# buckler.net
KiCad netlist of a schematic drawn in EAGLE
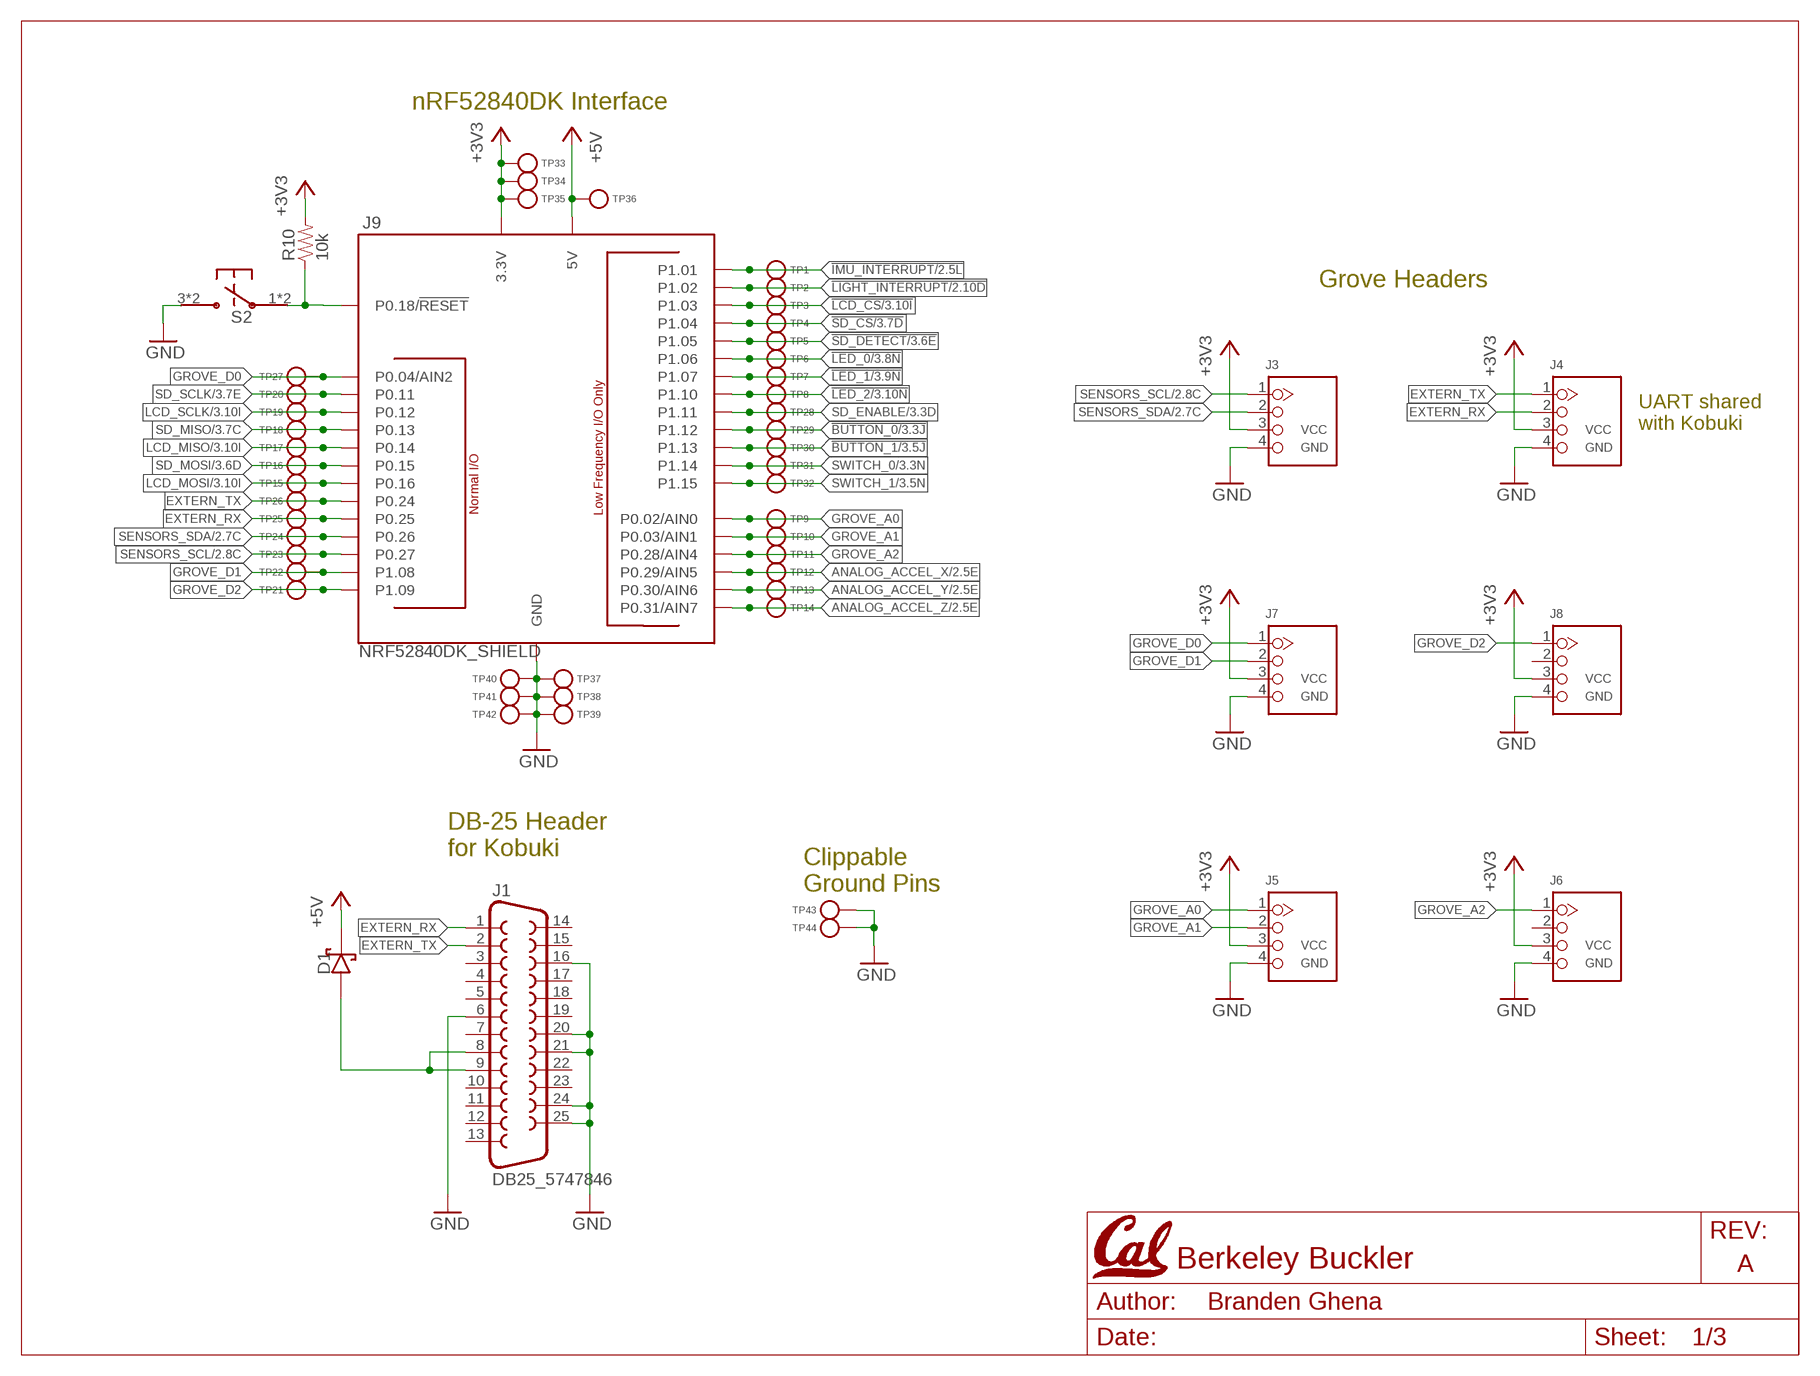
[diagram p0: schematic, sheet 1]
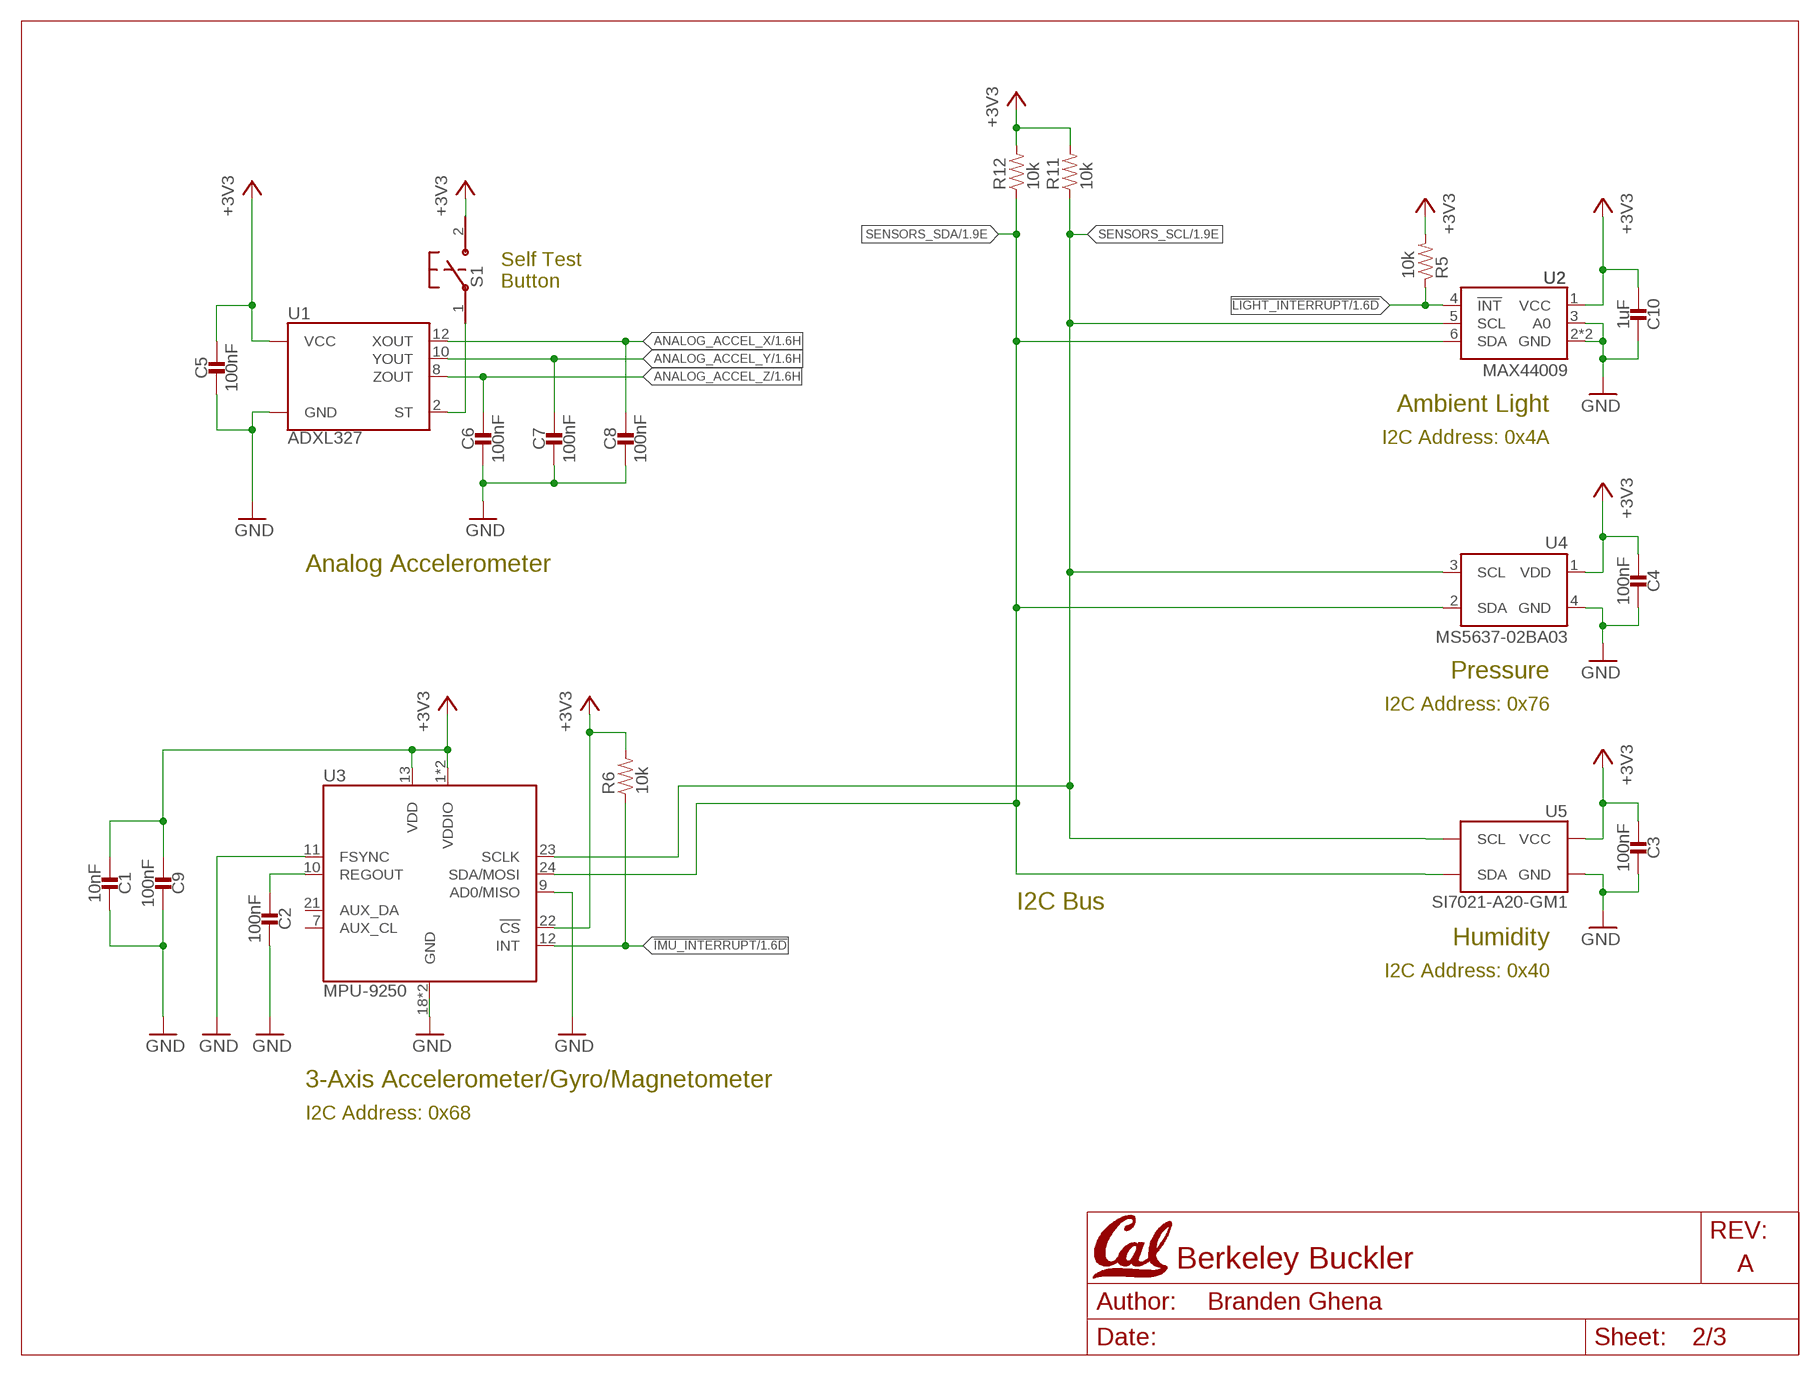
[diagram p1: schematic, sheet 2]
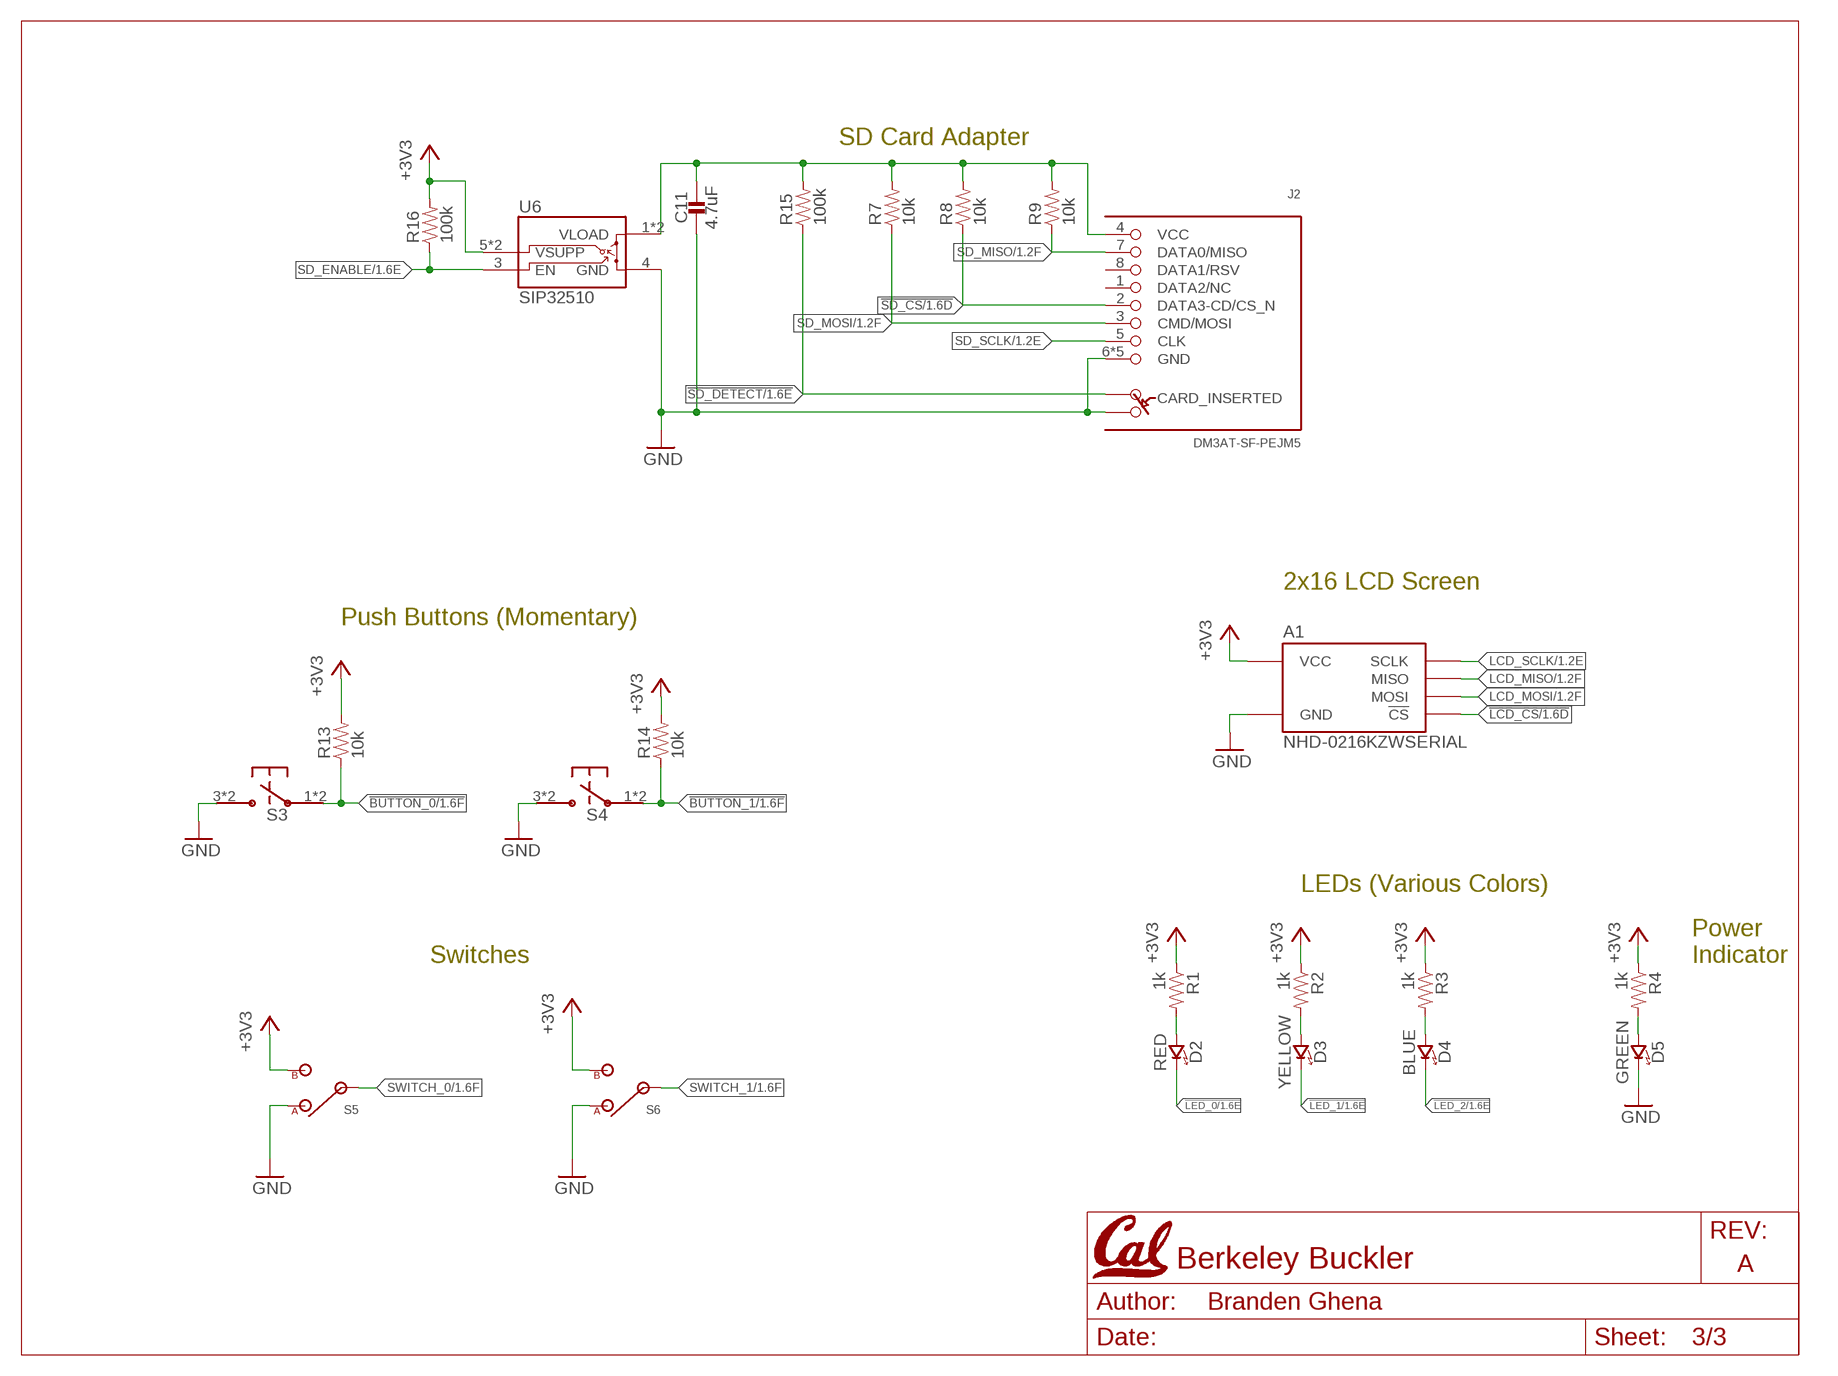
[diagram p2: schematic, sheet 3]

(export (version "E")
  (design (tool "Eeschema 10.0.6"))
  (components
    (comp (ref "D1")
      (value "DIODE_SCHOTTKYSOD323")
      (footprint "eagle-import:SOD323")
      (description "DIODE SCHOTTKY 30V 500MA SOD323")
      (fields (field (name "MANUFACTURER") "Diodes Incorporated") (field (name "MPN") "B0530WS-7-F"))
      (libsource (lib "eagle-import") (part "DIODE_SCHOTTKYSOD323"))
    )
    (comp (ref "J1")
      (value "DB25_5747846")
      (footprint "eagle-import:DB25_5747846")
      (description "CONN D-SUB RCPT 25POS R/A SOLDER")
      (fields (field (name "MANUFACTURER") "TE Connectivity AMP Connectors") (field (name "MPN") "5747846-4"))
      (libsource (lib "eagle-import") (part "DB25_5747846"))
    )
    (comp (ref "J3")
      (value "4P-2.0")
      (footprint "eagle-import:HW4-2.0")
      (description "Grove - Universal 4 pin connector")
      (fields (field (name "MANUFACTURER") "Seeed Studio") (field (name "MPN") "110990030"))
      (libsource (lib "eagle-import") (part "GROVE-CONNECTOR-DIP(4P-2.0)"))
    )
    (comp (ref "J4")
      (value "4P-2.0")
      (footprint "eagle-import:HW4-2.0")
      (description "Grove - Universal 4 pin connector")
      (fields (field (name "MANUFACTURER") "Seeed Studio") (field (name "MPN") "110990030"))
      (libsource (lib "eagle-import") (part "GROVE-CONNECTOR-DIP(4P-2.0)"))
    )
    (comp (ref "J5")
      (value "4P-2.0")
      (footprint "eagle-import:HW4-2.0")
      (description "Grove - Universal 4 pin connector")
      (fields (field (name "MANUFACTURER") "Seeed Studio") (field (name "MPN") "110990030"))
      (libsource (lib "eagle-import") (part "GROVE-CONNECTOR-DIP(4P-2.0)"))
    )
    (comp (ref "J6")
      (value "4P-2.0")
      (footprint "eagle-import:HW4-2.0")
      (description "Grove - Universal 4 pin connector")
      (fields (field (name "MANUFACTURER") "Seeed Studio") (field (name "MPN") "110990030"))
      (libsource (lib "eagle-import") (part "GROVE-CONNECTOR-DIP(4P-2.0)"))
    )
    (comp (ref "J7")
      (value "4P-2.0")
      (footprint "eagle-import:HW4-2.0")
      (description "Grove - Universal 4 pin connector")
      (fields (field (name "MANUFACTURER") "Seeed Studio") (field (name "MPN") "110990030"))
      (libsource (lib "eagle-import") (part "GROVE-CONNECTOR-DIP(4P-2.0)"))
    )
    (comp (ref "J8")
      (value "4P-2.0")
      (footprint "eagle-import:HW4-2.0")
      (description "Grove - Universal 4 pin connector")
      (fields (field (name "MANUFACTURER") "Seeed Studio") (field (name "MPN") "110990030"))
      (libsource (lib "eagle-import") (part "GROVE-CONNECTOR-DIP(4P-2.0)"))
    )
    (comp (ref "J9")
      (value "NRF52840DK_SHIELD")
      (footprint "eagle-import:NRF52840DK_SHIELD")
      (description "Headers for nRF52840DK. There are 6 separate headers to be installed through the board.")
      (libsource (lib "eagle-import") (part "NRF52840DK_SHIELD"))
    )
    (comp (ref "R10")
      (value "10k")
      (footprint "eagle-import:0402_RES")
      (description "RES SMD 10K OHM 1% 1/16W 0402")
      (fields (field (name "MANUFACTURER") "Samsung Electro-Mechanics") (field (name "MPN") "RC1005F103CS"))
      (libsource (lib "eagle-import") (part "RESISTOR0402_RES"))
    )
    (comp (ref "S2")
      (value "PTS645SM43SMTR92")
      (footprint "eagle-import:PTS645")
      (description "SWITCH TACTILE SPST-NO 0.05A 12V")
      (fields (field (name "MANUFACTURER") "C&K") (field (name "MPN") "PTS645SM43SMTR92 LFS"))
      (libsource (lib "eagle-import") (part "PTS645SM43SMTR92"))
    )
    (comp (ref "TP1")
      (value "TEST_POINT_0.040IN")
      (footprint "eagle-import:TESTPOINT_0.040IN")
      (libsource (lib "eagle-import") (part "TEST_POINT_0.040IN"))
    )
    (comp (ref "TP2")
      (value "TEST_POINT_0.040IN")
      (footprint "eagle-import:TESTPOINT_0.040IN")
      (libsource (lib "eagle-import") (part "TEST_POINT_0.040IN"))
    )
    (comp (ref "TP3")
      (value "TEST_POINT_0.040IN")
      (footprint "eagle-import:TESTPOINT_0.040IN")
      (libsource (lib "eagle-import") (part "TEST_POINT_0.040IN"))
    )
    (comp (ref "TP4")
      (value "TEST_POINT_0.040IN")
      (footprint "eagle-import:TESTPOINT_0.040IN")
      (libsource (lib "eagle-import") (part "TEST_POINT_0.040IN"))
    )
    (comp (ref "TP5")
      (value "TEST_POINT_0.040IN")
      (footprint "eagle-import:TESTPOINT_0.040IN")
      (libsource (lib "eagle-import") (part "TEST_POINT_0.040IN"))
    )
    (comp (ref "TP6")
      (value "TEST_POINT_0.040IN")
      (footprint "eagle-import:TESTPOINT_0.040IN")
      (libsource (lib "eagle-import") (part "TEST_POINT_0.040IN"))
    )
    (comp (ref "TP7")
      (value "TEST_POINT_0.040IN")
      (footprint "eagle-import:TESTPOINT_0.040IN")
      (libsource (lib "eagle-import") (part "TEST_POINT_0.040IN"))
    )
    (comp (ref "TP8")
      (value "TEST_POINT_0.040IN")
      (footprint "eagle-import:TESTPOINT_0.040IN")
      (libsource (lib "eagle-import") (part "TEST_POINT_0.040IN"))
    )
    (comp (ref "TP9")
      (value "TEST_POINT_0.040IN")
      (footprint "eagle-import:TESTPOINT_0.040IN")
      (libsource (lib "eagle-import") (part "TEST_POINT_0.040IN"))
    )
    (comp (ref "TP10")
      (value "TEST_POINT_0.040IN")
      (footprint "eagle-import:TESTPOINT_0.040IN")
      (libsource (lib "eagle-import") (part "TEST_POINT_0.040IN"))
    )
    (comp (ref "TP11")
      (value "TEST_POINT_0.040IN")
      (footprint "eagle-import:TESTPOINT_0.040IN")
      (libsource (lib "eagle-import") (part "TEST_POINT_0.040IN"))
    )
    (comp (ref "TP12")
      (value "TEST_POINT_0.040IN")
      (footprint "eagle-import:TESTPOINT_0.040IN")
      (libsource (lib "eagle-import") (part "TEST_POINT_0.040IN"))
    )
    (comp (ref "TP13")
      (value "TEST_POINT_0.040IN")
      (footprint "eagle-import:TESTPOINT_0.040IN")
      (libsource (lib "eagle-import") (part "TEST_POINT_0.040IN"))
    )
    (comp (ref "TP14")
      (value "TEST_POINT_0.040IN")
      (footprint "eagle-import:TESTPOINT_0.040IN")
      (libsource (lib "eagle-import") (part "TEST_POINT_0.040IN"))
    )
    (comp (ref "TP15")
      (value "TEST_POINT_0.040IN")
      (footprint "eagle-import:TESTPOINT_0.040IN")
      (libsource (lib "eagle-import") (part "TEST_POINT_0.040IN"))
    )
    (comp (ref "TP16")
      (value "TEST_POINT_0.040IN")
      (footprint "eagle-import:TESTPOINT_0.040IN")
      (libsource (lib "eagle-import") (part "TEST_POINT_0.040IN"))
    )
    (comp (ref "TP17")
      (value "TEST_POINT_0.040IN")
      (footprint "eagle-import:TESTPOINT_0.040IN")
      (libsource (lib "eagle-import") (part "TEST_POINT_0.040IN"))
    )
    (comp (ref "TP18")
      (value "TEST_POINT_0.040IN")
      (footprint "eagle-import:TESTPOINT_0.040IN")
      (libsource (lib "eagle-import") (part "TEST_POINT_0.040IN"))
    )
    (comp (ref "TP19")
      (value "TEST_POINT_0.040IN")
      (footprint "eagle-import:TESTPOINT_0.040IN")
      (libsource (lib "eagle-import") (part "TEST_POINT_0.040IN"))
    )
    (comp (ref "TP20")
      (value "TEST_POINT_0.040IN")
      (footprint "eagle-import:TESTPOINT_0.040IN")
      (libsource (lib "eagle-import") (part "TEST_POINT_0.040IN"))
    )
    (comp (ref "TP21")
      (value "TEST_POINT_0.040IN")
      (footprint "eagle-import:TESTPOINT_0.040IN")
      (libsource (lib "eagle-import") (part "TEST_POINT_0.040IN"))
    )
    (comp (ref "TP22")
      (value "TEST_POINT_0.040IN")
      (footprint "eagle-import:TESTPOINT_0.040IN")
      (libsource (lib "eagle-import") (part "TEST_POINT_0.040IN"))
    )
    (comp (ref "TP23")
      (value "TEST_POINT_0.040IN")
      (footprint "eagle-import:TESTPOINT_0.040IN")
      (libsource (lib "eagle-import") (part "TEST_POINT_0.040IN"))
    )
    (comp (ref "TP24")
      (value "TEST_POINT_0.040IN")
      (footprint "eagle-import:TESTPOINT_0.040IN")
      (libsource (lib "eagle-import") (part "TEST_POINT_0.040IN"))
    )
    (comp (ref "TP25")
      (value "TEST_POINT_0.040IN")
      (footprint "eagle-import:TESTPOINT_0.040IN")
      (libsource (lib "eagle-import") (part "TEST_POINT_0.040IN"))
    )
    (comp (ref "TP26")
      (value "TEST_POINT_0.040IN")
      (footprint "eagle-import:TESTPOINT_0.040IN")
      (libsource (lib "eagle-import") (part "TEST_POINT_0.040IN"))
    )
    (comp (ref "TP27")
      (value "TEST_POINT_0.040IN")
      (footprint "eagle-import:TESTPOINT_0.040IN")
      (libsource (lib "eagle-import") (part "TEST_POINT_0.040IN"))
    )
    (comp (ref "TP28")
      (value "TEST_POINT_0.040IN")
      (footprint "eagle-import:TESTPOINT_0.040IN")
      (libsource (lib "eagle-import") (part "TEST_POINT_0.040IN"))
    )
    (comp (ref "TP29")
      (value "TEST_POINT_0.040IN")
      (footprint "eagle-import:TESTPOINT_0.040IN")
      (libsource (lib "eagle-import") (part "TEST_POINT_0.040IN"))
    )
    (comp (ref "TP30")
      (value "TEST_POINT_0.040IN")
      (footprint "eagle-import:TESTPOINT_0.040IN")
      (libsource (lib "eagle-import") (part "TEST_POINT_0.040IN"))
    )
    (comp (ref "TP31")
      (value "TEST_POINT_0.040IN")
      (footprint "eagle-import:TESTPOINT_0.040IN")
      (libsource (lib "eagle-import") (part "TEST_POINT_0.040IN"))
    )
    (comp (ref "TP32")
      (value "TEST_POINT_0.040IN")
      (footprint "eagle-import:TESTPOINT_0.040IN")
      (libsource (lib "eagle-import") (part "TEST_POINT_0.040IN"))
    )
    (comp (ref "TP33")
      (value "TEST_POINT_0.040IN")
      (footprint "eagle-import:TESTPOINT_0.040IN")
      (libsource (lib "eagle-import") (part "TEST_POINT_0.040IN"))
    )
    (comp (ref "TP34")
      (value "TEST_POINT_0.040IN")
      (footprint "eagle-import:TESTPOINT_0.040IN")
      (libsource (lib "eagle-import") (part "TEST_POINT_0.040IN"))
    )
    (comp (ref "TP35")
      (value "TEST_POINT_0.040IN")
      (footprint "eagle-import:TESTPOINT_0.040IN")
      (libsource (lib "eagle-import") (part "TEST_POINT_0.040IN"))
    )
    (comp (ref "TP36")
      (value "TEST_POINT_0.040IN")
      (footprint "eagle-import:TESTPOINT_0.040IN")
      (libsource (lib "eagle-import") (part "TEST_POINT_0.040IN"))
    )
    (comp (ref "TP37")
      (value "TEST_POINT_0.040IN")
      (footprint "eagle-import:TESTPOINT_0.040IN")
      (libsource (lib "eagle-import") (part "TEST_POINT_0.040IN"))
    )
    (comp (ref "TP38")
      (value "TEST_POINT_0.040IN")
      (footprint "eagle-import:TESTPOINT_0.040IN")
      (libsource (lib "eagle-import") (part "TEST_POINT_0.040IN"))
    )
    (comp (ref "TP39")
      (value "TEST_POINT_0.040IN")
      (footprint "eagle-import:TESTPOINT_0.040IN")
      (libsource (lib "eagle-import") (part "TEST_POINT_0.040IN"))
    )
    (comp (ref "TP40")
      (value "TEST_POINT_0.040IN")
      (footprint "eagle-import:TESTPOINT_0.040IN")
      (libsource (lib "eagle-import") (part "TEST_POINT_0.040IN"))
    )
    (comp (ref "TP41")
      (value "TEST_POINT_0.040IN")
      (footprint "eagle-import:TESTPOINT_0.040IN")
      (libsource (lib "eagle-import") (part "TEST_POINT_0.040IN"))
    )
    (comp (ref "TP42")
      (value "TEST_POINT_0.040IN")
      (footprint "eagle-import:TESTPOINT_0.040IN")
      (libsource (lib "eagle-import") (part "TEST_POINT_0.040IN"))
    )
    (comp (ref "TP43")
      (value "TEST_POINT_0.078IN")
      (footprint "eagle-import:TESTPOINT_0.078IN")
      (description "TERM TURRET SINGLE L=4.75MM TIN")
      (fields (field (name "MANUFACTURER") "Keystone Electronics") (field (name "MPN") "1520-2"))
      (libsource (lib "eagle-import") (part "TEST_POINT_0.078IN"))
    )
    (comp (ref "TP44")
      (value "TEST_POINT_0.078IN")
      (footprint "eagle-import:TESTPOINT_0.078IN")
      (description "TERM TURRET SINGLE L=4.75MM TIN")
      (fields (field (name "MANUFACTURER") "Keystone Electronics") (field (name "MPN") "1520-2"))
      (libsource (lib "eagle-import") (part "TEST_POINT_0.078IN"))
    )
    (comp (ref "A1")
      (value "NHD-0216KZWSERIAL")
      (footprint "eagle-import:NHD-0216KZW")
      (libsource (lib "eagle-import") (part "NHD-0216KZWSERIAL"))
    )
    (comp (ref "C11")
      (value "4.7uF")
      (footprint "eagle-import:0402_CAP")
      (description "CAP CER 4.7UF 10V X5R 0402")
      (fields
        (field (name "MANUFACTURER") "Samsung Electro-Mechanics")
        (field (name "MPN") "CL05A475KP5NRNC")
      )
      (libsource (lib "eagle-import") (part "CAPACITOR0402_CAP"))
    )
    (comp (ref "D2")
      (value "RED")
      (footprint "eagle-import:LED-0603")
      (description "LED RED CLEAR CHIP SMD")
      (fields (field (name "MANUFACTURER") "Lite-On Inc.") (field (name "MPN") "LTST-C190KRKT"))
      (libsource (lib "eagle-import") (part "LED0603"))
    )
    (comp (ref "D3")
      (value "YELLOW")
      (footprint "eagle-import:LED-0603")
      (description "LED YELLOW CLEAR CHIP SMD")
      (fields (field (name "MANUFACTURER") "Lite-On Inc.") (field (name "MPN") "LTST-C190KSKT"))
      (libsource (lib "eagle-import") (part "LED0603"))
    )
    (comp (ref "D4")
      (value "BLUE")
      (footprint "eagle-import:LED-0603")
      (description "LED BLUE CLEAR SMD")
      (fields (field (name "MANUFACTURER") "Lite-On Inc.") (field (name "MPN") "LTST-C194TBKT"))
      (libsource (lib "eagle-import") (part "LED0603"))
    )
    (comp (ref "D5")
      (value "GREEN")
      (footprint "eagle-import:LED-0603")
      (description "LED GREEN CLEAR CHIP SMD")
      (fields (field (name "MANUFACTURER") "Lite-On Inc.") (field (name "MPN") "LTST-C190KGKT"))
      (libsource (lib "eagle-import") (part "LED0603"))
    )
    (comp (ref "J2")
      (value "DM3AT-SF-PEJM5")
      (footprint "eagle-import:DM3AT-SF-PEJM5")
      (fields (field (name "MANUFACTURER") "Hirose Electric Co Ltd"))
      (libsource (lib "eagle-import") (part "DM3AT-SF-PEJM5"))
    )
    (comp (ref "R1")
      (value "1k")
      (footprint "eagle-import:0402_RES")
      (description "RES SMD 1K OHM 1% 1/16W 0402")
      (fields (field (name "MANUFACTURER") "Stackpole Electronics") (field (name "MPN") "RMCF0402FT1K00"))
      (libsource (lib "eagle-import") (part "RESISTOR0402_RES"))
    )
    (comp (ref "R2")
      (value "1k")
      (footprint "eagle-import:0402_RES")
      (description "RES SMD 1K OHM 1% 1/16W 0402")
      (fields (field (name "MANUFACTURER") "Stackpole Electronics") (field (name "MPN") "RMCF0402FT1K00"))
      (libsource (lib "eagle-import") (part "RESISTOR0402_RES"))
    )
    (comp (ref "R3")
      (value "1k")
      (footprint "eagle-import:0402_RES")
      (description "RES SMD 1K OHM 1% 1/16W 0402")
      (fields (field (name "MANUFACTURER") "Stackpole Electronics") (field (name "MPN") "RMCF0402FT1K00"))
      (libsource (lib "eagle-import") (part "RESISTOR0402_RES"))
    )
    (comp (ref "R4")
      (value "1k")
      (footprint "eagle-import:0402_RES")
      (description "RES SMD 1K OHM 1% 1/16W 0402")
      (fields (field (name "MANUFACTURER") "Stackpole Electronics") (field (name "MPN") "RMCF0402FT1K00"))
      (libsource (lib "eagle-import") (part "RESISTOR0402_RES"))
    )
    (comp (ref "R7")
      (value "10k")
      (footprint "eagle-import:0402_RES")
      (description "RES SMD 10K OHM 1% 1/16W 0402")
      (fields (field (name "MANUFACTURER") "Samsung Electro-Mechanics") (field (name "MPN") "RC1005F103CS"))
      (libsource (lib "eagle-import") (part "RESISTOR0402_RES"))
    )
    (comp (ref "R8")
      (value "10k")
      (footprint "eagle-import:0402_RES")
      (description "RES SMD 10K OHM 1% 1/16W 0402")
      (fields (field (name "MANUFACTURER") "Samsung Electro-Mechanics") (field (name "MPN") "RC1005F103CS"))
      (libsource (lib "eagle-import") (part "RESISTOR0402_RES"))
    )
    (comp (ref "R9")
      (value "10k")
      (footprint "eagle-import:0402_RES")
      (description "RES SMD 10K OHM 1% 1/16W 0402")
      (fields (field (name "MANUFACTURER") "Samsung Electro-Mechanics") (field (name "MPN") "RC1005F103CS"))
      (libsource (lib "eagle-import") (part "RESISTOR0402_RES"))
    )
    (comp (ref "R13")
      (value "10k")
      (footprint "eagle-import:0402_RES")
      (description "RES SMD 10K OHM 1% 1/16W 0402")
      (fields (field (name "MANUFACTURER") "Samsung Electro-Mechanics") (field (name "MPN") "RC1005F103CS"))
      (libsource (lib "eagle-import") (part "RESISTOR0402_RES"))
    )
    (comp (ref "R14")
      (value "10k")
      (footprint "eagle-import:0402_RES")
      (description "RES SMD 10K OHM 1% 1/16W 0402")
      (fields (field (name "MANUFACTURER") "Samsung Electro-Mechanics") (field (name "MPN") "RC1005F103CS"))
      (libsource (lib "eagle-import") (part "RESISTOR0402_RES"))
    )
    (comp (ref "R15")
      (value "100k")
      (footprint "eagle-import:0402_RES")
      (description "RES SMD 100K OHM 1% 1/5W 0402")
      (fields (field (name "MANUFACTURER") "Vishay Dale") (field (name "MPN") "CRCW0402100KFKEDHP"))
      (libsource (lib "eagle-import") (part "RESISTOR0402_RES"))
    )
    (comp (ref "R16")
      (value "100k")
      (footprint "eagle-import:0402_RES")
      (description "RES SMD 100K OHM 1% 1/5W 0402")
      (fields (field (name "MANUFACTURER") "Vishay Dale") (field (name "MPN") "CRCW0402100KFKEDHP"))
      (libsource (lib "eagle-import") (part "RESISTOR0402_RES"))
    )
    (comp (ref "S3")
      (value "PTS645SM43SMTR92")
      (footprint "eagle-import:PTS645")
      (description "SWITCH TACTILE SPST-NO 0.05A 12V")
      (fields (field (name "MANUFACTURER") "C&K") (field (name "MPN") "PTS645SM43SMTR92 LFS"))
      (libsource (lib "eagle-import") (part "PTS645SM43SMTR92"))
    )
    (comp (ref "S4")
      (value "PTS645SM43SMTR92")
      (footprint "eagle-import:PTS645")
      (description "SWITCH TACTILE SPST-NO 0.05A 12V")
      (fields (field (name "MANUFACTURER") "C&K") (field (name "MPN") "PTS645SM43SMTR92 LFS"))
      (libsource (lib "eagle-import") (part "PTS645SM43SMTR92"))
    )
    (comp (ref "S5")
      (value "TE_SSA12/SPDT")
      (footprint "eagle-import:TE_SSA12_SPDT")
      (description "SWITCH SLIDE SPDT 100MA 30V")
      (fields
        (field (name "MANUFACTURER") "TE Connectivity ALCOSWITCH Switches")
        (field (name "MPN") "SSA12")
      )
      (libsource (lib "eagle-import") (part "TE_SSA12/SPDT"))
    )
    (comp (ref "S6")
      (value "TE_SSA12/SPDT")
      (footprint "eagle-import:TE_SSA12_SPDT")
      (description "SWITCH SLIDE SPDT 100MA 30V")
      (fields
        (field (name "MANUFACTURER") "TE Connectivity ALCOSWITCH Switches")
        (field (name "MPN") "SSA12")
      )
      (libsource (lib "eagle-import") (part "TE_SSA12/SPDT"))
    )
    (comp (ref "U6")
      (value "SIP32510")
      (footprint "eagle-import:TSOT23-6")
      (description "IC LOAD SWITCH SOT23-6")
      (fields (field (name "MANUFACTURER") "Vishay") (field (name "MPN") "SIP32510DT-T1-GE3"))
      (libsource (lib "eagle-import") (part "SIP32510"))
    )
    (comp (ref "C1")
      (value "10nF")
      (footprint "eagle-import:0402_CAP")
      (description "CAP CER 10000PF 25V X7R 0402")
      (fields (field (name "MANUFACTURER") "KEMET") (field (name "MPN") "C0402C103J3RACTU"))
      (libsource (lib "eagle-import") (part "CAPACITOR0402_CAP"))
    )
    (comp (ref "C2")
      (value "100nF")
      (footprint "eagle-import:0402_CAP")
      (description "CAP CER 0.1UF 16V X7R 0402")
      (fields (field (name "MANUFACTURER") "Murata") (field (name "MPN") "GCM155R71C104KA55D"))
      (libsource (lib "eagle-import") (part "CAPACITOR0402_CAP"))
    )
    (comp (ref "C3")
      (value "100nF")
      (footprint "eagle-import:0402_CAP")
      (description "CAP CER 0.1UF 16V X7R 0402")
      (fields (field (name "MANUFACTURER") "Murata") (field (name "MPN") "GCM155R71C104KA55D"))
      (libsource (lib "eagle-import") (part "CAPACITOR0402_CAP"))
    )
    (comp (ref "C4")
      (value "100nF")
      (footprint "eagle-import:0402_CAP")
      (description "CAP CER 0.1UF 16V X7R 0402")
      (fields (field (name "MANUFACTURER") "Murata") (field (name "MPN") "GCM155R71C104KA55D"))
      (libsource (lib "eagle-import") (part "CAPACITOR0402_CAP"))
    )
    (comp (ref "C5")
      (value "100nF")
      (footprint "eagle-import:0402_CAP")
      (description "CAP CER 0.1UF 16V X7R 0402")
      (fields (field (name "MANUFACTURER") "Murata") (field (name "MPN") "GCM155R71C104KA55D"))
      (libsource (lib "eagle-import") (part "CAPACITOR0402_CAP"))
    )
    (comp (ref "C6")
      (value "100nF")
      (footprint "eagle-import:0402_CAP")
      (description "CAP CER 0.1UF 16V X7R 0402")
      (fields (field (name "MANUFACTURER") "Murata") (field (name "MPN") "GCM155R71C104KA55D"))
      (libsource (lib "eagle-import") (part "CAPACITOR0402_CAP"))
    )
    (comp (ref "C7")
      (value "100nF")
      (footprint "eagle-import:0402_CAP")
      (description "CAP CER 0.1UF 16V X7R 0402")
      (fields (field (name "MANUFACTURER") "Murata") (field (name "MPN") "GCM155R71C104KA55D"))
      (libsource (lib "eagle-import") (part "CAPACITOR0402_CAP"))
    )
    (comp (ref "C8")
      (value "100nF")
      (footprint "eagle-import:0402_CAP")
      (description "CAP CER 0.1UF 16V X7R 0402")
      (fields (field (name "MANUFACTURER") "Murata") (field (name "MPN") "GCM155R71C104KA55D"))
      (libsource (lib "eagle-import") (part "CAPACITOR0402_CAP"))
    )
    (comp (ref "C9")
      (value "100nF")
      (footprint "eagle-import:0402_CAP")
      (description "CAP CER 0.1UF 16V X7R 0402")
      (fields (field (name "MANUFACTURER") "Murata") (field (name "MPN") "GCM155R71C104KA55D"))
      (libsource (lib "eagle-import") (part "CAPACITOR0402_CAP"))
    )
    (comp (ref "C10")
      (value "1uF")
      (footprint "eagle-import:0402_CAP")
      (description "CAP CER 1UF 10V X6S 0402")
      (fields
        (field (name "MANUFACTURER") "Samsung Electro-Mechanics")
        (field (name "MPN") "CL05X105KP5NNNC")
      )
      (libsource (lib "eagle-import") (part "CAPACITOR0402_CAP"))
    )
    (comp (ref "R5")
      (value "10k")
      (footprint "eagle-import:0402_RES")
      (description "RES SMD 10K OHM 1% 1/16W 0402")
      (fields (field (name "MANUFACTURER") "Samsung Electro-Mechanics") (field (name "MPN") "RC1005F103CS"))
      (libsource (lib "eagle-import") (part "RESISTOR0402_RES"))
    )
    (comp (ref "R6")
      (value "10k")
      (footprint "eagle-import:0402_RES")
      (description "RES SMD 10K OHM 1% 1/16W 0402")
      (fields (field (name "MANUFACTURER") "Samsung Electro-Mechanics") (field (name "MPN") "RC1005F103CS"))
      (libsource (lib "eagle-import") (part "RESISTOR0402_RES"))
    )
    (comp (ref "R11")
      (value "10k")
      (footprint "eagle-import:0402_RES")
      (description "RES SMD 10K OHM 1% 1/16W 0402")
      (fields (field (name "MANUFACTURER") "Samsung Electro-Mechanics") (field (name "MPN") "RC1005F103CS"))
      (libsource (lib "eagle-import") (part "RESISTOR0402_RES"))
    )
    (comp (ref "R12")
      (value "10k")
      (footprint "eagle-import:0402_RES")
      (description "RES SMD 10K OHM 1% 1/16W 0402")
      (fields (field (name "MANUFACTURER") "Samsung Electro-Mechanics") (field (name "MPN") "RC1005F103CS"))
      (libsource (lib "eagle-import") (part "RESISTOR0402_RES"))
    )
    (comp (ref "S1")
      (value "B3U-1000P")
      (footprint "eagle-import:B3U-1000P")
      (description "SWITCH TACTILE SPST-NO 0.05A 12V")
      (fields (field (name "MANUFACTURER") "Omron") (field (name "MPN") "B3U-1000P"))
      (libsource (lib "eagle-import") (part "B3U-1000P"))
    )
    (comp (ref "U1")
      (value "ADXL327")
      (footprint "eagle-import:LFCSP-16")
      (description "ACCELEROMETER 2G ANALOG 16LFCSP")
      (fields (field (name "MANUFACTURER") "Analog Devices Inc.") (field (name "MPN") "ADXL327BCPZ"))
      (libsource (lib "eagle-import") (part "ADXL327"))
    )
    (comp (ref "U2")
      (value "MAX44009")
      (footprint "eagle-import:UDFN-6-EXPOSED")
      (description "SENSOR AMBIENT LIGHT 6UTDFN")
      (fields
        (field (name "MANUFACTURER") "MAXIM")
        (field (name "MPN") "MAX44009EDT+T")
        (field (name "MANUFACTURER_1") "Maxim Integrated")
      )
      (libsource (lib "eagle-import") (part "MAX44009"))
    )
    (comp (ref "U3")
      (value "MPU-9250")
      (footprint "eagle-import:QFN-24_3MM")
      (description "IMU ACCEL/GYRO/MAG I2C/SPI 24QFN")
      (fields (field (name "MANUFACTURER") "TDK InvenSense"))
      (libsource (lib "eagle-import") (part "MPU-9250"))
    )
    (comp (ref "U4")
      (value "MS5637-02BA03")
      (footprint "eagle-import:4-SMD")
      (description "SENSOR 17.4PSIA I2C 24B 4-QFN")
      (fields (field (name "MANUFACTURER") "TE CONNECTIVITY") (field (name "MPN") "MS563702BA03-50"))
      (libsource (lib "eagle-import") (part "MS5637-02BA03"))
    )
    (comp (ref "U5")
      (value "SI7021-A20-GM1")
      (footprint "eagle-import:DFN-6_3MM")
      (description "SENS HUMI/TEMP 3.6V I2C 3% 6DFN")
      (fields (field (name "MANUFACTURER") "Silicon Labs") (field (name "MPN") "SI7021-A20-GM1 "))
      (libsource (lib "eagle-import") (part "SI7021-A20-GM1"))
    )
  )
  (nets
    (net (code "1") (name "+3V3") (class "Default")
      (node (ref "A1") (pin "2") (pinfunction "VCC_2") (pintype "bidirectional"))
      (node (ref "C1") (pin "1") (pinfunction "1_1") (pintype "bidirectional"))
      (node (ref "C10") (pin "1") (pinfunction "1_1") (pintype "bidirectional"))
      (node (ref "C3") (pin "1") (pinfunction "1_1") (pintype "bidirectional"))
      (node (ref "C4") (pin "1") (pinfunction "1_1") (pintype "bidirectional"))
      (node (ref "C5") (pin "1") (pinfunction "1_1") (pintype "bidirectional"))
      (node (ref "C9") (pin "1") (pinfunction "1_1") (pintype "bidirectional"))
      (node (ref "J3") (pin "3") (pinfunction "3_3") (pintype "bidirectional"))
      (node (ref "J4") (pin "3") (pinfunction "3_3") (pintype "bidirectional"))
      (node (ref "J5") (pin "3") (pinfunction "3_3") (pintype "bidirectional"))
      (node (ref "J6") (pin "3") (pinfunction "3_3") (pintype "bidirectional"))
      (node (ref "J7") (pin "3") (pinfunction "3_3") (pintype "bidirectional"))
      (node (ref "J8") (pin "3") (pinfunction "3_3") (pintype "bidirectional"))
      (node (ref "J9") (pin "3.3V@0") (pinfunction "3.3V_3.3V@0") (pintype "bidirectional"))
      (node (ref "J9") (pin "3.3V@1") (pinfunction "3.3V_3.3V@1") (pintype "bidirectional"))
      (node (ref "J9") (pin "3.3V@2") (pinfunction "3.3V_3.3V@2") (pintype "bidirectional"))
      (node (ref "R1") (pin "1") (pinfunction "1_1") (pintype "passive"))
      (node (ref "R10") (pin "2") (pinfunction "2_2") (pintype "passive"))
      (node (ref "R11") (pin "2") (pinfunction "2_2") (pintype "passive"))
      (node (ref "R12") (pin "2") (pinfunction "2_2") (pintype "passive"))
      (node (ref "R13") (pin "2") (pinfunction "2_2") (pintype "passive"))
      (node (ref "R14") (pin "2") (pinfunction "2_2") (pintype "passive"))
      (node (ref "R16") (pin "2") (pinfunction "2_2") (pintype "passive"))
      (node (ref "R2") (pin "1") (pinfunction "1_1") (pintype "passive"))
      (node (ref "R3") (pin "1") (pinfunction "1_1") (pintype "passive"))
      (node (ref "R4") (pin "1") (pinfunction "1_1") (pintype "passive"))
      (node (ref "R5") (pin "2") (pinfunction "2_2") (pintype "passive"))
      (node (ref "R6") (pin "2") (pinfunction "2_2") (pintype "passive"))
      (node (ref "S1") (pin "2") (pinfunction "P$2_2") (pintype "passive"))
      (node (ref "S5") (pin "2") (pinfunction "B_2") (pintype "bidirectional"))
      (node (ref "S6") (pin "2") (pinfunction "B_2") (pintype "bidirectional"))
      (node (ref "TP33") (pin "TESTPOINT") (pinfunction "TESTPOINT_TESTPOINT") (pintype "bidirectional"))
      (node (ref "TP34") (pin "TESTPOINT") (pinfunction "TESTPOINT_TESTPOINT") (pintype "bidirectional"))
      (node (ref "TP35") (pin "TESTPOINT") (pinfunction "TESTPOINT_TESTPOINT") (pintype "bidirectional"))
      (node (ref "U1") (pin "14") (pinfunction "VCC_14") (pintype "bidirectional"))
      (node (ref "U1") (pin "15") (pinfunction "VCC_15") (pintype "bidirectional"))
      (node (ref "U2") (pin "1") (pinfunction "VCC_1") (pintype "bidirectional"))
      (node (ref "U3") (pin "1") (pinfunction "VDDIO_1") (pintype "bidirectional"))
      (node (ref "U3") (pin "13") (pinfunction "VDD_13") (pintype "bidirectional"))
      (node (ref "U3") (pin "22") (pinfunction "~{CS}_22") (pintype "bidirectional"))
      (node (ref "U3") (pin "8") (pinfunction "VDDIO_8") (pintype "bidirectional"))
      (node (ref "U4") (pin "1") (pinfunction "VDD_1") (pintype "bidirectional"))
      (node (ref "U5") (pin "5") (pinfunction "VCC_5") (pintype "bidirectional"))
      (node (ref "U6") (pin "5") (pinfunction "VSUPP_5") (pintype "bidirectional"))
      (node (ref "U6") (pin "6") (pinfunction "VSUPP_6") (pintype "bidirectional"))
    )
    (net (code "2") (name "+5V") (class "Default")
      (node (ref "D1") (pin "P$1") (pinfunction "CATHODE_P$1") (pintype "bidirectional"))
      (node (ref "J9") (pin "5V") (pinfunction "5V_5V") (pintype "bidirectional"))
      (node (ref "TP36") (pin "TESTPOINT") (pinfunction "TESTPOINT_TESTPOINT") (pintype "bidirectional"))
    )
    (net (code "3") (name "ANALOG_ACCEL_X") (class "Default")
      (node (ref "C8") (pin "1") (pinfunction "1_1") (pintype "bidirectional"))
      (node (ref "J9") (pin "P0.29") (pinfunction "P0.29/AIN5_P0.29") (pintype "bidirectional"))
      (node (ref "TP12") (pin "TESTPOINT") (pinfunction "TESTPOINT_TESTPOINT") (pintype "bidirectional"))
      (node (ref "U1") (pin "12") (pinfunction "XOUT_12") (pintype "bidirectional"))
    )
    (net (code "4") (name "ANALOG_ACCEL_Y") (class "Default")
      (node (ref "C7") (pin "1") (pinfunction "1_1") (pintype "bidirectional"))
      (node (ref "J9") (pin "P0.30") (pinfunction "P0.30/AIN6_P0.30") (pintype "bidirectional"))
      (node (ref "TP13") (pin "TESTPOINT") (pinfunction "TESTPOINT_TESTPOINT") (pintype "bidirectional"))
      (node (ref "U1") (pin "10") (pinfunction "YOUT_10") (pintype "bidirectional"))
    )
    (net (code "5") (name "ANALOG_ACCEL_Z") (class "Default")
      (node (ref "C6") (pin "1") (pinfunction "1_1") (pintype "bidirectional"))
      (node (ref "J9") (pin "P0.31") (pinfunction "P0.31/AIN7_P0.31") (pintype "bidirectional"))
      (node (ref "TP14") (pin "TESTPOINT") (pinfunction "TESTPOINT_TESTPOINT") (pintype "bidirectional"))
      (node (ref "U1") (pin "8") (pinfunction "ZOUT_8") (pintype "bidirectional"))
    )
    (net (code "6") (name "EXTERN_RX") (class "Default")
      (node (ref "J1") (pin "1") (pinfunction "1_1") (pintype "passive"))
      (node (ref "J4") (pin "2") (pinfunction "2_2") (pintype "bidirectional"))
      (node (ref "J9") (pin "P0.25") (pinfunction "P0.25_P0.25") (pintype "bidirectional"))
      (node (ref "TP25") (pin "TESTPOINT") (pinfunction "TESTPOINT_TESTPOINT") (pintype "bidirectional"))
    )
    (net (code "7") (name "EXTERN_TX") (class "Default")
      (node (ref "J1") (pin "2") (pinfunction "2_2") (pintype "passive"))
      (node (ref "J4") (pin "1") (pinfunction "1_1") (pintype "bidirectional"))
      (node (ref "J9") (pin "P0.24") (pinfunction "P0.24_P0.24") (pintype "bidirectional"))
      (node (ref "TP26") (pin "TESTPOINT") (pinfunction "TESTPOINT_TESTPOINT") (pintype "bidirectional"))
    )
    (net (code "8") (name "GND") (class "Default")
      (node (ref "A1") (pin "1") (pinfunction "GND_1") (pintype "bidirectional"))
      (node (ref "C1") (pin "2") (pinfunction "2_2") (pintype "bidirectional"))
      (node (ref "C10") (pin "2") (pinfunction "2_2") (pintype "bidirectional"))
      (node (ref "C11") (pin "2") (pinfunction "2_2") (pintype "bidirectional"))
      (node (ref "C2") (pin "2") (pinfunction "2_2") (pintype "bidirectional"))
      (node (ref "C3") (pin "2") (pinfunction "2_2") (pintype "bidirectional"))
      (node (ref "C4") (pin "2") (pinfunction "2_2") (pintype "bidirectional"))
      (node (ref "C5") (pin "2") (pinfunction "2_2") (pintype "bidirectional"))
      (node (ref "C6") (pin "2") (pinfunction "2_2") (pintype "bidirectional"))
      (node (ref "C7") (pin "2") (pinfunction "2_2") (pintype "bidirectional"))
      (node (ref "C8") (pin "2") (pinfunction "2_2") (pintype "bidirectional"))
      (node (ref "C9") (pin "2") (pinfunction "2_2") (pintype "bidirectional"))
      (node (ref "D5") (pin "C") (pinfunction "CATHODE_C") (pintype "bidirectional"))
      (node (ref "J1") (pin "16") (pinfunction "16_16") (pintype "passive"))
      (node (ref "J1") (pin "20") (pinfunction "20_20") (pintype "passive"))
      (node (ref "J1") (pin "21") (pinfunction "21_21") (pintype "passive"))
      (node (ref "J1") (pin "24") (pinfunction "24_24") (pintype "passive"))
      (node (ref "J1") (pin "25") (pinfunction "25_25") (pintype "passive"))
      (node (ref "J1") (pin "6") (pinfunction "6_6") (pintype "passive"))
      (node (ref "J2") (pin "6") (pinfunction "GND_6") (pintype "bidirectional"))
      (node (ref "J2") (pin "B") (pinfunction "B_B") (pintype "bidirectional"))
      (node (ref "J2") (pin "MOUNT0") (pinfunction "GND_MOUNT0") (pintype "bidirectional"))
      (node (ref "J2") (pin "MOUNT1") (pinfunction "GND_MOUNT1") (pintype "bidirectional"))
      (node (ref "J2") (pin "MOUNT2") (pinfunction "GND_MOUNT2") (pintype "bidirectional"))
      (node (ref "J2") (pin "MOUNT3") (pinfunction "GND_MOUNT3") (pintype "bidirectional"))
      (node (ref "J3") (pin "4") (pinfunction "4_4") (pintype "bidirectional"))
      (node (ref "J4") (pin "4") (pinfunction "4_4") (pintype "bidirectional"))
      (node (ref "J5") (pin "4") (pinfunction "4_4") (pintype "bidirectional"))
      (node (ref "J6") (pin "4") (pinfunction "4_4") (pintype "bidirectional"))
      (node (ref "J7") (pin "4") (pinfunction "4_4") (pintype "bidirectional"))
      (node (ref "J8") (pin "4") (pinfunction "4_4") (pintype "bidirectional"))
      (node (ref "J9") (pin "GND@0") (pinfunction "GND_GND@0") (pintype "bidirectional"))
      (node (ref "J9") (pin "GND@1") (pinfunction "GND_GND@1") (pintype "bidirectional"))
      (node (ref "J9") (pin "GND@2") (pinfunction "GND_GND@2") (pintype "bidirectional"))
      (node (ref "J9") (pin "GND@3") (pinfunction "GND_GND@3") (pintype "bidirectional"))
      (node (ref "S2") (pin "3") (pinfunction "P$2_3") (pintype "passive"))
      (node (ref "S2") (pin "4") (pinfunction "P$2_4") (pintype "passive"))
      (node (ref "S3") (pin "3") (pinfunction "P$2_3") (pintype "passive"))
      (node (ref "S3") (pin "4") (pinfunction "P$2_4") (pintype "passive"))
      (node (ref "S4") (pin "3") (pinfunction "P$2_3") (pintype "passive"))
      (node (ref "S4") (pin "4") (pinfunction "P$2_4") (pintype "passive"))
      (node (ref "S5") (pin "1") (pinfunction "A_1") (pintype "bidirectional"))
      (node (ref "S6") (pin "1") (pinfunction "A_1") (pintype "bidirectional"))
      (node (ref "TP37") (pin "TESTPOINT") (pinfunction "TESTPOINT_TESTPOINT") (pintype "bidirectional"))
      (node (ref "TP38") (pin "TESTPOINT") (pinfunction "TESTPOINT_TESTPOINT") (pintype "bidirectional"))
      (node (ref "TP39") (pin "TESTPOINT") (pinfunction "TESTPOINT_TESTPOINT") (pintype "bidirectional"))
      (node (ref "TP40") (pin "TESTPOINT") (pinfunction "TESTPOINT_TESTPOINT") (pintype "bidirectional"))
      (node (ref "TP41") (pin "TESTPOINT") (pinfunction "TESTPOINT_TESTPOINT") (pintype "bidirectional"))
      (node (ref "TP42") (pin "TESTPOINT") (pinfunction "TESTPOINT_TESTPOINT") (pintype "bidirectional"))
      (node (ref "TP43") (pin "1") (pinfunction "TESTPOINT_1") (pintype "bidirectional"))
      (node (ref "TP44") (pin "1") (pinfunction "TESTPOINT_1") (pintype "bidirectional"))
      (node (ref "U1") (pin "3") (pinfunction "GND_3") (pintype "bidirectional"))
      (node (ref "U1") (pin "5") (pinfunction "GND_5") (pintype "bidirectional"))
      (node (ref "U1") (pin "6") (pinfunction "GND_6") (pintype "bidirectional"))
      (node (ref "U1") (pin "7") (pinfunction "GND_7") (pintype "bidirectional"))
      (node (ref "U2") (pin "2") (pinfunction "GND_2") (pintype "bidirectional"))
      (node (ref "U2") (pin "3") (pinfunction "A0_3") (pintype "bidirectional"))
      (node (ref "U2") (pin "EP") (pinfunction "GND_EP") (pintype "bidirectional"))
      (node (ref "U3") (pin "11") (pinfunction "FSYNC_11") (pintype "bidirectional"))
      (node (ref "U3") (pin "18") (pinfunction "GND_18") (pintype "bidirectional"))
      (node (ref "U3") (pin "20") (pinfunction "GND_20") (pintype "bidirectional"))
      (node (ref "U3") (pin "9") (pinfunction "AD0/MISO_9") (pintype "bidirectional"))
      (node (ref "U4") (pin "4") (pinfunction "GND_4") (pintype "bidirectional"))
      (node (ref "U5") (pin "2") (pinfunction "GND_2") (pintype "bidirectional"))
      (node (ref "U6") (pin "4") (pinfunction "GND_4") (pintype "bidirectional"))
    )
    (net (code "9") (name "GROVE_A0") (class "Default")
      (node (ref "J5") (pin "1") (pinfunction "1_1") (pintype "bidirectional"))
      (node (ref "J9") (pin "P0.02") (pinfunction "P0.02/AIN0_P0.02") (pintype "bidirectional"))
      (node (ref "TP9") (pin "TESTPOINT") (pinfunction "TESTPOINT_TESTPOINT") (pintype "bidirectional"))
    )
    (net (code "10") (name "GROVE_A1") (class "Default")
      (node (ref "J5") (pin "2") (pinfunction "2_2") (pintype "bidirectional"))
      (node (ref "J9") (pin "P0.03") (pinfunction "P0.03/AIN1_P0.03") (pintype "bidirectional"))
      (node (ref "TP10") (pin "TESTPOINT") (pinfunction "TESTPOINT_TESTPOINT") (pintype "bidirectional"))
    )
    (net (code "11") (name "GROVE_A2") (class "Default")
      (node (ref "J6") (pin "1") (pinfunction "1_1") (pintype "bidirectional"))
      (node (ref "J9") (pin "P0.28") (pinfunction "P0.28/AIN4_P0.28") (pintype "bidirectional"))
      (node (ref "TP11") (pin "TESTPOINT") (pinfunction "TESTPOINT_TESTPOINT") (pintype "bidirectional"))
    )
    (net (code "12") (name "GROVE_D0") (class "Default")
      (node (ref "J7") (pin "1") (pinfunction "1_1") (pintype "bidirectional"))
      (node (ref "J9") (pin "P0.04") (pinfunction "P0.04/AIN2_P0.04") (pintype "bidirectional"))
      (node (ref "TP27") (pin "TESTPOINT") (pinfunction "TESTPOINT_TESTPOINT") (pintype "bidirectional"))
    )
    (net (code "13") (name "GROVE_D1") (class "Default")
      (node (ref "J7") (pin "2") (pinfunction "2_2") (pintype "bidirectional"))
      (node (ref "J9") (pin "P1.08") (pinfunction "P1.08_P1.08") (pintype "bidirectional"))
      (node (ref "TP22") (pin "TESTPOINT") (pinfunction "TESTPOINT_TESTPOINT") (pintype "bidirectional"))
    )
    (net (code "14") (name "GROVE_D2") (class "Default")
      (node (ref "J8") (pin "1") (pinfunction "1_1") (pintype "bidirectional"))
      (node (ref "J9") (pin "P1.09") (pinfunction "P1.09_P1.09") (pintype "bidirectional"))
      (node (ref "TP21") (pin "TESTPOINT") (pinfunction "TESTPOINT_TESTPOINT") (pintype "bidirectional"))
    )
    (net (code "15") (name "LCD_MISO") (class "Default")
      (node (ref "A1") (pin "13") (pinfunction "MISO_13") (pintype "bidirectional"))
      (node (ref "J9") (pin "P0.14") (pinfunction "P0.14_P0.14") (pintype "bidirectional"))
      (node (ref "TP17") (pin "TESTPOINT") (pinfunction "TESTPOINT_TESTPOINT") (pintype "bidirectional"))
    )
    (net (code "16") (name "LCD_MOSI") (class "Default")
      (node (ref "A1") (pin "14") (pinfunction "MOSI_14") (pintype "bidirectional"))
      (node (ref "J9") (pin "P0.16") (pinfunction "P0.16_P0.16") (pintype "bidirectional"))
      (node (ref "TP15") (pin "TESTPOINT") (pinfunction "TESTPOINT_TESTPOINT") (pintype "bidirectional"))
    )
    (net (code "17") (name "LCD_SCLK") (class "Default")
      (node (ref "A1") (pin "12") (pinfunction "SCLK_12") (pintype "bidirectional"))
      (node (ref "J9") (pin "P0.12") (pinfunction "P0.12_P0.12") (pintype "bidirectional"))
      (node (ref "TP19") (pin "TESTPOINT") (pinfunction "TESTPOINT_TESTPOINT") (pintype "bidirectional"))
    )
    (net (code "18") (name "Net-(D1-ANODE)") (class "Default")
      (node (ref "D1") (pin "P$2") (pinfunction "ANODE_P$2") (pintype "bidirectional"))
      (node (ref "J1") (pin "8") (pinfunction "8_8") (pintype "passive"))
      (node (ref "J1") (pin "9") (pinfunction "9_9") (pintype "passive"))
    )
    (net (code "19") (name "Net-(D2-ANODE)") (class "Default")
      (node (ref "D2") (pin "A") (pinfunction "ANODE_A") (pintype "bidirectional"))
      (node (ref "R1") (pin "2") (pinfunction "2_2") (pintype "passive"))
    )
    (net (code "20") (name "Net-(D3-ANODE)") (class "Default")
      (node (ref "D3") (pin "A") (pinfunction "ANODE_A") (pintype "bidirectional"))
      (node (ref "R2") (pin "2") (pinfunction "2_2") (pintype "passive"))
    )
    (net (code "21") (name "Net-(D4-ANODE)") (class "Default")
      (node (ref "D4") (pin "A") (pinfunction "ANODE_A") (pintype "bidirectional"))
      (node (ref "R3") (pin "2") (pinfunction "2_2") (pintype "passive"))
    )
    (net (code "22") (name "Net-(D5-ANODE)") (class "Default")
      (node (ref "D5") (pin "A") (pinfunction "ANODE_A") (pintype "bidirectional"))
      (node (ref "R4") (pin "2") (pinfunction "2_2") (pintype "passive"))
    )
    (net (code "23") (name "Net-(J2-VCC)") (class "Default")
      (node (ref "C11") (pin "1") (pinfunction "1_1") (pintype "bidirectional"))
      (node (ref "J2") (pin "4") (pinfunction "VCC_4") (pintype "bidirectional"))
      (node (ref "R15") (pin "2") (pinfunction "2_2") (pintype "passive"))
      (node (ref "R7") (pin "2") (pinfunction "2_2") (pintype "passive"))
      (node (ref "R8") (pin "2") (pinfunction "2_2") (pintype "passive"))
      (node (ref "R9") (pin "2") (pinfunction "2_2") (pintype "passive"))
      (node (ref "U6") (pin "1") (pinfunction "VLOAD_1") (pintype "bidirectional"))
      (node (ref "U6") (pin "2") (pinfunction "VLOAD_2") (pintype "bidirectional"))
    )
    (net (code "24") (name "Net-(J9-P0.18{slash}~{RESET})") (class "Default")
      (node (ref "J9") (pin "P0.18") (pinfunction "P0.18/~{RESET}_P0.18") (pintype "bidirectional"))
      (node (ref "R10") (pin "1") (pinfunction "1_1") (pintype "passive"))
      (node (ref "S2") (pin "1") (pinfunction "P$1_1") (pintype "passive"))
      (node (ref "S2") (pin "2") (pinfunction "P$1_2") (pintype "passive"))
    )
    (net (code "25") (name "Net-(S1-P$1)") (class "Default")
      (node (ref "S1") (pin "1") (pinfunction "P$1_1") (pintype "passive"))
      (node (ref "U1") (pin "2") (pinfunction "ST_2") (pintype "bidirectional"))
    )
    (net (code "26") (name "Net-(U3-REGOUT)") (class "Default")
      (node (ref "C2") (pin "1") (pinfunction "1_1") (pintype "bidirectional"))
      (node (ref "U3") (pin "10") (pinfunction "REGOUT_10") (pintype "bidirectional"))
    )
    (net (code "27") (name "SD_ENABLE") (class "Default")
      (node (ref "J9") (pin "P1.11") (pinfunction "P1.11_P1.11") (pintype "bidirectional"))
      (node (ref "R16") (pin "1") (pinfunction "1_1") (pintype "passive"))
      (node (ref "TP28") (pin "TESTPOINT") (pinfunction "TESTPOINT_TESTPOINT") (pintype "bidirectional"))
      (node (ref "U6") (pin "3") (pinfunction "EN_3") (pintype "bidirectional"))
    )
    (net (code "28") (name "SD_MISO") (class "Default")
      (node (ref "J2") (pin "7") (pinfunction "DATA0/MISO_7") (pintype "bidirectional"))
      (node (ref "J9") (pin "P0.13") (pinfunction "P0.13_P0.13") (pintype "bidirectional"))
      (node (ref "R9") (pin "1") (pinfunction "1_1") (pintype "passive"))
      (node (ref "TP18") (pin "TESTPOINT") (pinfunction "TESTPOINT_TESTPOINT") (pintype "bidirectional"))
    )
    (net (code "29") (name "SD_MOSI") (class "Default")
      (node (ref "J2") (pin "3") (pinfunction "CMD/MOSI_3") (pintype "bidirectional"))
      (node (ref "J9") (pin "P0.15") (pinfunction "P0.15_P0.15") (pintype "bidirectional"))
      (node (ref "R7") (pin "1") (pinfunction "1_1") (pintype "passive"))
      (node (ref "TP16") (pin "TESTPOINT") (pinfunction "TESTPOINT_TESTPOINT") (pintype "bidirectional"))
    )
    (net (code "30") (name "SD_SCLK") (class "Default")
      (node (ref "J2") (pin "5") (pinfunction "CLK_5") (pintype "bidirectional"))
      (node (ref "J9") (pin "P0.11") (pinfunction "P0.11_P0.11") (pintype "bidirectional"))
      (node (ref "TP20") (pin "TESTPOINT") (pinfunction "TESTPOINT_TESTPOINT") (pintype "bidirectional"))
    )
    (net (code "31") (name "SENSORS_SCL") (class "Default")
      (node (ref "J3") (pin "1") (pinfunction "1_1") (pintype "bidirectional"))
      (node (ref "J9") (pin "P0.27") (pinfunction "P0.27_P0.27") (pintype "bidirectional"))
      (node (ref "R11") (pin "1") (pinfunction "1_1") (pintype "passive"))
      (node (ref "TP23") (pin "TESTPOINT") (pinfunction "TESTPOINT_TESTPOINT") (pintype "bidirectional"))
      (node (ref "U2") (pin "5") (pinfunction "SCL_5") (pintype "bidirectional"))
      (node (ref "U3") (pin "23") (pinfunction "SCLK_23") (pintype "bidirectional"))
      (node (ref "U4") (pin "3") (pinfunction "SCL_3") (pintype "bidirectional"))
      (node (ref "U5") (pin "6") (pinfunction "SCL_6") (pintype "bidirectional"))
    )
    (net (code "32") (name "SENSORS_SDA") (class "Default")
      (node (ref "J3") (pin "2") (pinfunction "2_2") (pintype "bidirectional"))
      (node (ref "J9") (pin "P0.26") (pinfunction "P0.26_P0.26") (pintype "bidirectional"))
      (node (ref "R12") (pin "1") (pinfunction "1_1") (pintype "passive"))
      (node (ref "TP24") (pin "TESTPOINT") (pinfunction "TESTPOINT_TESTPOINT") (pintype "bidirectional"))
      (node (ref "U2") (pin "6") (pinfunction "SDA_6") (pintype "bidirectional"))
      (node (ref "U3") (pin "24") (pinfunction "SDA/MOSI_24") (pintype "bidirectional"))
      (node (ref "U4") (pin "2") (pinfunction "SDA_2") (pintype "bidirectional"))
      (node (ref "U5") (pin "1") (pinfunction "SDA_1") (pintype "bidirectional"))
    )
    (net (code "33") (name "SWITCH_0") (class "Default")
      (node (ref "J9") (pin "P1.14") (pinfunction "P1.14_P1.14") (pintype "bidirectional"))
      (node (ref "S5") (pin "IN") (pinfunction "IN_IN") (pintype "bidirectional"))
      (node (ref "TP31") (pin "TESTPOINT") (pinfunction "TESTPOINT_TESTPOINT") (pintype "bidirectional"))
    )
    (net (code "34") (name "SWITCH_1") (class "Default")
      (node (ref "J9") (pin "P1.15") (pinfunction "P1.15_P1.15") (pintype "bidirectional"))
      (node (ref "S6") (pin "IN") (pinfunction "IN_IN") (pintype "bidirectional"))
      (node (ref "TP32") (pin "TESTPOINT") (pinfunction "TESTPOINT_TESTPOINT") (pintype "bidirectional"))
    )
    (net (code "35") (name "unconnected-(J1-Pad3)") (class "Default")
      (node (ref "J1") (pin "3") (pinfunction "3_3") (pintype "passive"))
    )
    (net (code "36") (name "unconnected-(J1-Pad4)") (class "Default")
      (node (ref "J1") (pin "4") (pinfunction "4_4") (pintype "passive"))
    )
    (net (code "37") (name "unconnected-(J1-Pad5)") (class "Default")
      (node (ref "J1") (pin "5") (pinfunction "5_5") (pintype "passive"))
    )
    (net (code "38") (name "unconnected-(J1-Pad7)") (class "Default")
      (node (ref "J1") (pin "7") (pinfunction "7_7") (pintype "passive"))
    )
    (net (code "39") (name "unconnected-(J1-Pad10)") (class "Default")
      (node (ref "J1") (pin "10") (pinfunction "10_10") (pintype "passive"))
    )
    (net (code "40") (name "unconnected-(J1-Pad11)") (class "Default")
      (node (ref "J1") (pin "11") (pinfunction "11_11") (pintype "passive"))
    )
    (net (code "41") (name "unconnected-(J1-Pad12)") (class "Default")
      (node (ref "J1") (pin "12") (pinfunction "12_12") (pintype "passive"))
    )
    (net (code "42") (name "unconnected-(J1-Pad13)") (class "Default")
      (node (ref "J1") (pin "13") (pinfunction "13_13") (pintype "passive"))
    )
    (net (code "43") (name "unconnected-(J1-Pad14)") (class "Default")
      (node (ref "J1") (pin "14") (pinfunction "14_14") (pintype "passive"))
    )
    (net (code "44") (name "unconnected-(J1-Pad15)") (class "Default")
      (node (ref "J1") (pin "15") (pinfunction "15_15") (pintype "passive"))
    )
    (net (code "45") (name "unconnected-(J1-Pad17)") (class "Default")
      (node (ref "J1") (pin "17") (pinfunction "17_17") (pintype "passive"))
    )
    (net (code "46") (name "unconnected-(J1-Pad18)") (class "Default")
      (node (ref "J1") (pin "18") (pinfunction "18_18") (pintype "passive"))
    )
    (net (code "47") (name "unconnected-(J1-Pad19)") (class "Default")
      (node (ref "J1") (pin "19") (pinfunction "19_19") (pintype "passive"))
    )
    (net (code "48") (name "unconnected-(J1-Pad22)") (class "Default")
      (node (ref "J1") (pin "22") (pinfunction "22_22") (pintype "passive"))
    )
    (net (code "49") (name "unconnected-(J1-Pad23)") (class "Default")
      (node (ref "J1") (pin "23") (pinfunction "23_23") (pintype "passive"))
    )
    (net (code "50") (name "unconnected-(J2-DATA1{slash}RSV-Pad8)") (class "Default")
      (node (ref "J2") (pin "8") (pinfunction "DATA1/RSV_8") (pintype "bidirectional"))
    )
    (net (code "51") (name "unconnected-(J2-DATA2{slash}NC-Pad1)") (class "Default")
      (node (ref "J2") (pin "1") (pinfunction "DATA2/NC_1") (pintype "bidirectional"))
    )
    (net (code "52") (name "unconnected-(J6-Pad2)") (class "Default")
      (node (ref "J6") (pin "2") (pinfunction "2_2") (pintype "bidirectional"))
    )
    (net (code "53") (name "unconnected-(J8-Pad2)") (class "Default")
      (node (ref "J8") (pin "2") (pinfunction "2_2") (pintype "bidirectional"))
    )
    (net (code "54") (name "unconnected-(U3-AUX_CL-Pad7)") (class "Default")
      (node (ref "U3") (pin "7") (pinfunction "AUX_CL_7") (pintype "bidirectional"))
    )
    (net (code "55") (name "unconnected-(U3-AUX_DA-Pad21)") (class "Default")
      (node (ref "U3") (pin "21") (pinfunction "AUX_DA_21") (pintype "bidirectional"))
    )
    (net (code "56") (name "~{BUTTON_0}") (class "Default")
      (node (ref "J9") (pin "P1.12") (pinfunction "P1.12_P1.12") (pintype "bidirectional"))
      (node (ref "R13") (pin "1") (pinfunction "1_1") (pintype "passive"))
      (node (ref "S3") (pin "1") (pinfunction "P$1_1") (pintype "passive"))
      (node (ref "S3") (pin "2") (pinfunction "P$1_2") (pintype "passive"))
      (node (ref "TP29") (pin "TESTPOINT") (pinfunction "TESTPOINT_TESTPOINT") (pintype "bidirectional"))
    )
    (net (code "57") (name "~{BUTTON_1}") (class "Default")
      (node (ref "J9") (pin "P1.13") (pinfunction "P1.13_P1.13") (pintype "bidirectional"))
      (node (ref "R14") (pin "1") (pinfunction "1_1") (pintype "passive"))
      (node (ref "S4") (pin "1") (pinfunction "P$1_1") (pintype "passive"))
      (node (ref "S4") (pin "2") (pinfunction "P$1_2") (pintype "passive"))
      (node (ref "TP30") (pin "TESTPOINT") (pinfunction "TESTPOINT_TESTPOINT") (pintype "bidirectional"))
    )
    (net (code "58") (name "~{IMU_INTERRUPT}") (class "Default")
      (node (ref "J9") (pin "P1.01") (pinfunction "P1.01_P1.01") (pintype "bidirectional"))
      (node (ref "R6") (pin "1") (pinfunction "1_1") (pintype "passive"))
      (node (ref "TP1") (pin "TESTPOINT") (pinfunction "TESTPOINT_TESTPOINT") (pintype "bidirectional"))
      (node (ref "U3") (pin "12") (pinfunction "INT_12") (pintype "bidirectional"))
    )
    (net (code "59") (name "~{LCD_CS}") (class "Default")
      (node (ref "A1") (pin "16") (pinfunction "~{CS}_16") (pintype "bidirectional"))
      (node (ref "J9") (pin "P1.03") (pinfunction "P1.03_P1.03") (pintype "bidirectional"))
      (node (ref "TP3") (pin "TESTPOINT") (pinfunction "TESTPOINT_TESTPOINT") (pintype "bidirectional"))
    )
    (net (code "60") (name "~{LED_0}") (class "Default")
      (node (ref "D2") (pin "C") (pinfunction "CATHODE_C") (pintype "bidirectional"))
      (node (ref "J9") (pin "P1.06") (pinfunction "P1.06_P1.06") (pintype "bidirectional"))
      (node (ref "TP6") (pin "TESTPOINT") (pinfunction "TESTPOINT_TESTPOINT") (pintype "bidirectional"))
    )
    (net (code "61") (name "~{LED_1}") (class "Default")
      (node (ref "D3") (pin "C") (pinfunction "CATHODE_C") (pintype "bidirectional"))
      (node (ref "J9") (pin "P1.07") (pinfunction "P1.07_P1.07") (pintype "bidirectional"))
      (node (ref "TP7") (pin "TESTPOINT") (pinfunction "TESTPOINT_TESTPOINT") (pintype "bidirectional"))
    )
    (net (code "62") (name "~{LED_2}") (class "Default")
      (node (ref "D4") (pin "C") (pinfunction "CATHODE_C") (pintype "bidirectional"))
      (node (ref "J9") (pin "P1.10") (pinfunction "P1.10_P1.10") (pintype "bidirectional"))
      (node (ref "TP8") (pin "TESTPOINT") (pinfunction "TESTPOINT_TESTPOINT") (pintype "bidirectional"))
    )
    (net (code "63") (name "~{LIGHT_INTERRUPT}") (class "Default")
      (node (ref "J9") (pin "P1.02") (pinfunction "P1.02_P1.02") (pintype "bidirectional"))
      (node (ref "R5") (pin "1") (pinfunction "1_1") (pintype "passive"))
      (node (ref "TP2") (pin "TESTPOINT") (pinfunction "TESTPOINT_TESTPOINT") (pintype "bidirectional"))
      (node (ref "U2") (pin "4") (pinfunction "~{INT}_4") (pintype "bidirectional"))
    )
    (net (code "64") (name "~{SD_CS}") (class "Default")
      (node (ref "J2") (pin "2") (pinfunction "DATA3-CD/CS_N_2") (pintype "bidirectional"))
      (node (ref "J9") (pin "P1.04") (pinfunction "P1.04_P1.04") (pintype "bidirectional"))
      (node (ref "R8") (pin "1") (pinfunction "1_1") (pintype "passive"))
      (node (ref "TP4") (pin "TESTPOINT") (pinfunction "TESTPOINT_TESTPOINT") (pintype "bidirectional"))
    )
    (net (code "65") (name "~{SD_DETECT}") (class "Default")
      (node (ref "J2") (pin "A") (pinfunction "A_A") (pintype "bidirectional"))
      (node (ref "J9") (pin "P1.05") (pinfunction "P1.05_P1.05") (pintype "bidirectional"))
      (node (ref "R15") (pin "1") (pinfunction "1_1") (pintype "passive"))
      (node (ref "TP5") (pin "TESTPOINT") (pinfunction "TESTPOINT_TESTPOINT") (pintype "bidirectional"))
    )
  )
)
